# Water_Bird_wagtail.net
KiCad netlist of a schematic drawn in EAGLE
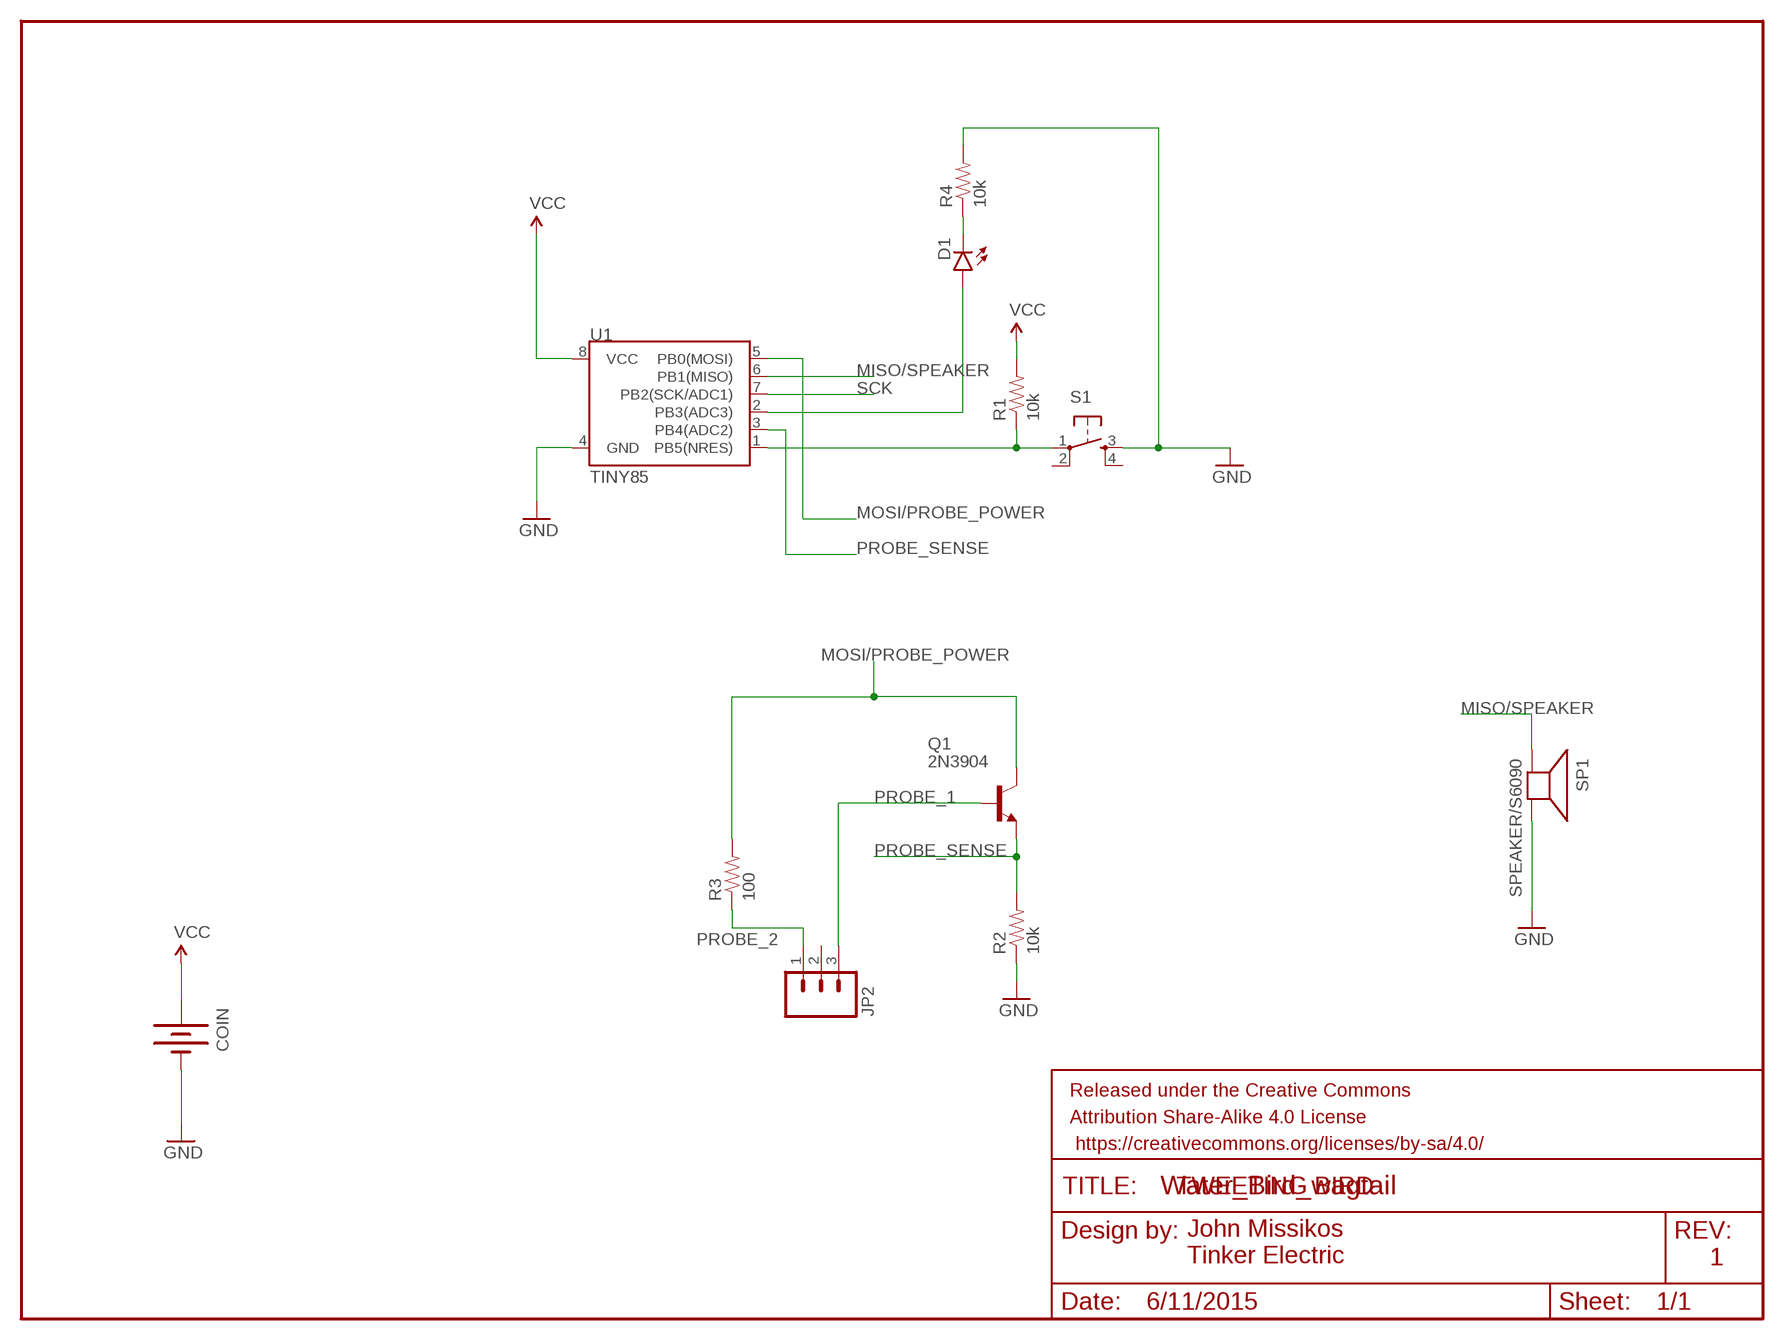
[diagram p0: schematic, sheet 1]

(export (version "E")
  (design (tool "Eeschema 10.0.6"))
  (components
    (comp (ref "COIN")
      (value "BATTERY_20MM20PTH")
      (footprint "eagle-import:BATTCOM_20MM_PTH")
      (libsource (lib "eagle-import") (part "BATTERY_20MM20PTH"))
    )
    (comp (ref "D1")
      (value "LED5MM")
      (footprint "eagle-import:LED5MM")
      (libsource (lib "eagle-import") (part "LED5MM"))
    )
    (comp (ref "FRAME1")
      (value "FRAME-LETTERNO_PACKAGE")
      (footprint "eagle-import:DUMMY")
      (fields (field (name "DESIGNER") "JM"))
      (libsource (lib "eagle-import") (part "FRAME-LETTERNO_PACKAGE"))
    )
    (comp (ref "JP2")
      (value "M03-SCREW-5MM")
      (footprint "eagle-import:SCREWTERMINAL-5MM-3")
      (libsource (lib "eagle-import") (part "M03-SCREW-5MM"))
    )
    (comp (ref "Q1")
      (value "2N3904")
      (footprint "eagle-import:TO92-EBC-OVAL")
      (libsource (lib "eagle-import") (part "2N2222"))
    )
    (comp (ref "R1")
      (value "10k")
      (footprint "eagle-import:AXIAL-0.3")
      (libsource (lib "eagle-import") (part "RESISTORAXIAL-0.3"))
    )
    (comp (ref "R2")
      (value "10k")
      (footprint "eagle-import:AXIAL-0.3")
      (libsource (lib "eagle-import") (part "RESISTORAXIAL-0.3"))
    )
    (comp (ref "R3")
      (value "100")
      (footprint "eagle-import:AXIAL-0.3")
      (libsource (lib "eagle-import") (part "RESISTORAXIAL-0.3"))
    )
    (comp (ref "R4")
      (value "10k")
      (footprint "eagle-import:AXIAL-0.3")
      (libsource (lib "eagle-import") (part "RESISTORAXIAL-0.3"))
    )
    (comp (ref "S1")
      (value "TAC_SWITCHPTH")
      (footprint "eagle-import:TACTILE-PTH")
      (libsource (lib "eagle-import") (part "TAC_SWITCHPTH"))
    )
    (comp (ref "SP1")
      (value "SPEAKER/S6090")
      (footprint "eagle-import:S6090")
      (libsource (lib "eagle-import") (part "SPEAKER/S6090"))
    )
    (comp (ref "U1")
      (value "TINY85")
      (footprint "eagle-import:DIP08")
      (libsource (lib "eagle-import") (part "ATTINY45TINY85-20-DIP"))
    )
  )
  (nets
    (net (code "1") (name "/MISO{slash}SPEAKER") (class "Default")
      (node (ref "SP1") (pin "1") (pinfunction "+_1") (pintype "passive"))
      (node (ref "U1") (pin "6") (pinfunction "PB1(MISO)_6") (pintype "bidirectional"))
    )
    (net (code "2") (name "/MOSI{slash}PROBE_POWER") (class "Default")
      (node (ref "Q1") (pin "C") (pinfunction "C_C") (pintype "passive"))
      (node (ref "R3") (pin "P$2") (pinfunction "2_P$2") (pintype "passive"))
      (node (ref "U1") (pin "5") (pinfunction "PB0(MOSI)_5") (pintype "bidirectional"))
    )
    (net (code "3") (name "/PROBE_1") (class "Default")
      (node (ref "JP2") (pin "3") (pinfunction "3_3") (pintype "passive"))
      (node (ref "Q1") (pin "B") (pinfunction "B_B") (pintype "passive"))
    )
    (net (code "4") (name "/PROBE_2") (class "Default")
      (node (ref "JP2") (pin "1") (pinfunction "1_1") (pintype "passive"))
      (node (ref "R3") (pin "P$1") (pinfunction "1_P$1") (pintype "passive"))
    )
    (net (code "5") (name "/PROBE_SENSE") (class "Default")
      (node (ref "Q1") (pin "E") (pinfunction "E_E") (pintype "passive"))
      (node (ref "R2") (pin "P$2") (pinfunction "2_P$2") (pintype "passive"))
      (node (ref "U1") (pin "3") (pinfunction "PB4(ADC2)_3") (pintype "bidirectional"))
    )
    (net (code "6") (name "/SCK") (class "Default")
      (node (ref "U1") (pin "7") (pinfunction "PB2(SCK/ADC1)_7") (pintype "bidirectional"))
    )
    (net (code "7") (name "GND") (class "Default")
      (node (ref "COIN") (pin "2") (pinfunction "-_2") (pintype "power_in"))
      (node (ref "R2") (pin "P$1") (pinfunction "1_P$1") (pintype "passive"))
      (node (ref "R4") (pin "P$2") (pinfunction "2_P$2") (pintype "passive"))
      (node (ref "S1") (pin "3") (pinfunction "3_3") (pintype "passive"))
      (node (ref "SP1") (pin "2") (pinfunction "-_2") (pintype "passive"))
      (node (ref "U1") (pin "4") (pinfunction "GND_4") (pintype "bidirectional"))
    )
    (net (code "8") (name "Net-(D1-C)") (class "Default")
      (node (ref "D1") (pin "K") (pinfunction "C_K") (pintype "passive"))
      (node (ref "R4") (pin "P$1") (pinfunction "1_P$1") (pintype "passive"))
    )
    (net (code "9") (name "Net-(R1-1)") (class "Default")
      (node (ref "R1") (pin "P$1") (pinfunction "1_P$1") (pintype "passive"))
      (node (ref "S1") (pin "1") (pinfunction "1_1") (pintype "passive"))
      (node (ref "U1") (pin "1") (pinfunction "PB5(NRES)_1") (pintype "bidirectional"))
    )
    (net (code "10") (name "Net-(U1-PB3(ADC3))") (class "Default")
      (node (ref "D1") (pin "A") (pinfunction "A_A") (pintype "passive"))
      (node (ref "U1") (pin "2") (pinfunction "PB3(ADC3)_2") (pintype "bidirectional"))
    )
    (net (code "11") (name "VCC") (class "Default")
      (node (ref "COIN") (pin "1") (pinfunction "+_1") (pintype "power_in"))
      (node (ref "R1") (pin "P$2") (pinfunction "2_P$2") (pintype "passive"))
      (node (ref "U1") (pin "8") (pinfunction "VCC_8") (pintype "bidirectional"))
    )
    (net (code "12") (name "unconnected-(JP2-Pad2)") (class "Default")
      (node (ref "JP2") (pin "2") (pinfunction "2_2") (pintype "passive"))
    )
    (net (code "13") (name "unconnected-(S1-Pad2)") (class "Default")
      (node (ref "S1") (pin "2") (pinfunction "2_2") (pintype "passive"))
    )
    (net (code "14") (name "unconnected-(S1-Pad4)") (class "Default")
      (node (ref "S1") (pin "4") (pinfunction "4_4") (pintype "passive"))
    )
  )
)
